# ConnWB.net
KiCad netlist of a schematic drawn in Altium Designer
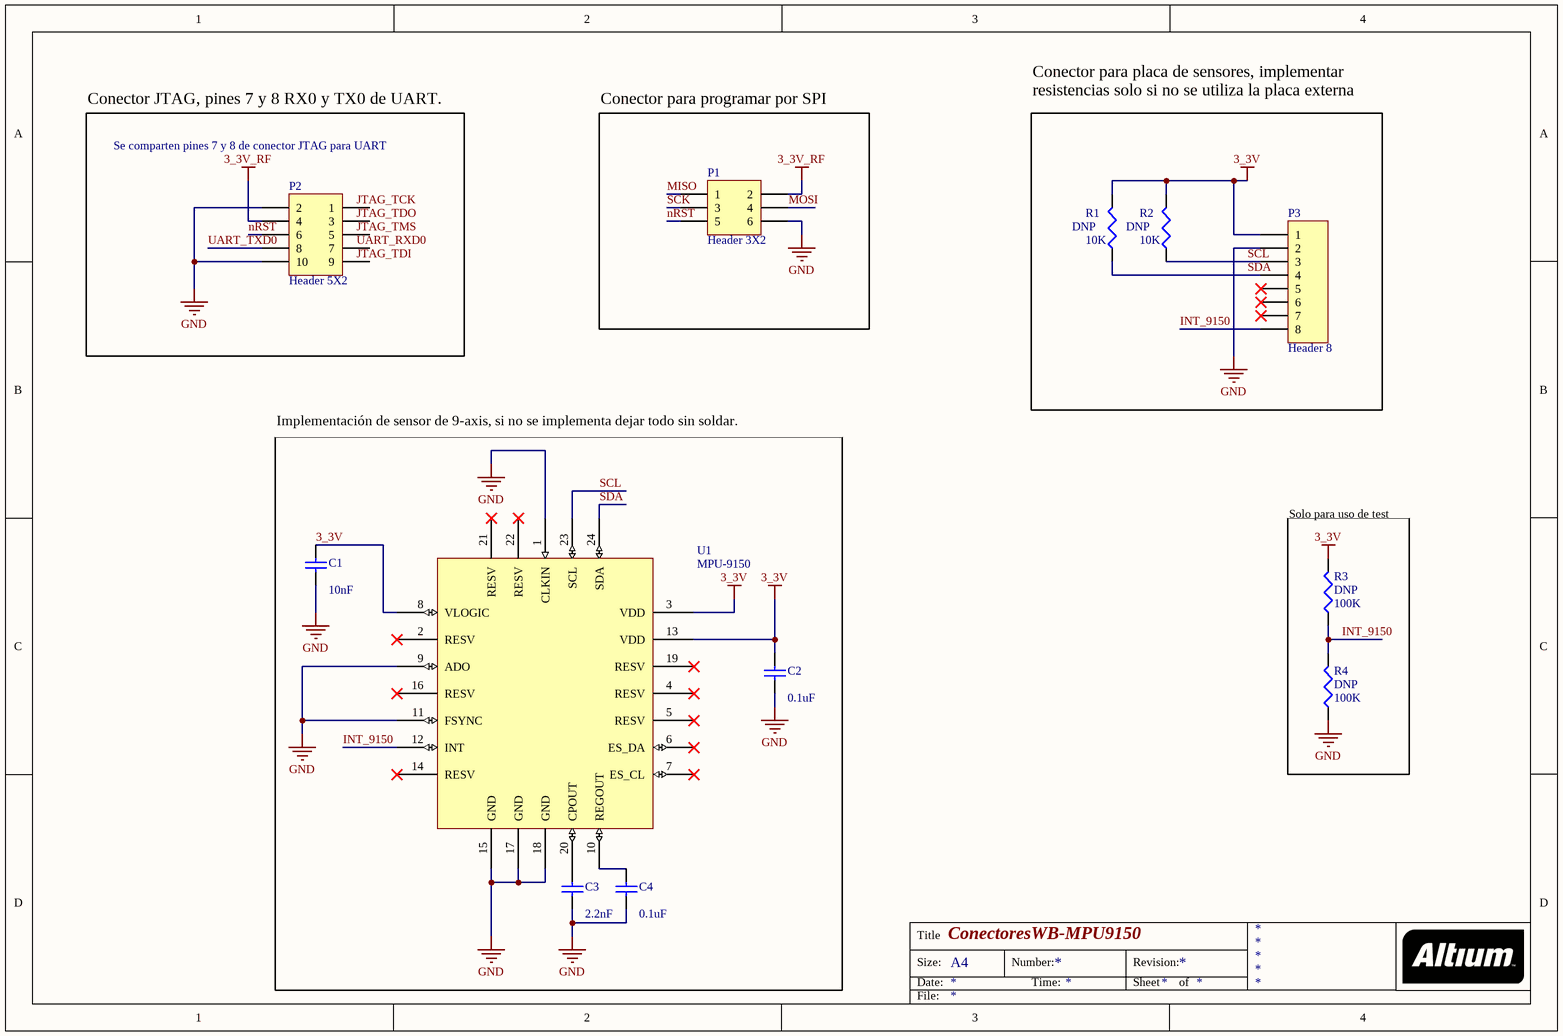
[diagram p0: ConnWB.SchDoc]

(export (version "E")
  (design (tool "Eeschema 10.0.6"))
  (components
    (comp (ref "C1")
      (value "10nF")
      (footprint "1608[0603]")
      (description "Capacitor (Semiconductor SIM Model)")
      (fields (field (name "Comment") "Cap Semi") (field (name "PUBLISHER") "Altium Limited"))
      (libsource (lib "Miscellaneous Devices") (part "Cap Semi"))
    )
    (comp (ref "C2")
      (value "0.1uF")
      (footprint "C1206")
      (description "Capacitor (Semiconductor SIM Model)")
      (fields (field (name "Comment") "Cap Semi") (field (name "PUBLISHER") "Altium Limited"))
      (libsource (lib "Miscellaneous Devices") (part "Cap Semi"))
    )
    (comp (ref "C3")
      (value "2.2nF")
      (footprint "1608[0603]")
      (description "Capacitor (Semiconductor SIM Model)")
      (fields (field (name "Comment") "Cap Semi") (field (name "PUBLISHER") "Altium Limited"))
      (libsource (lib "Miscellaneous Devices") (part "Cap Semi"))
    )
    (comp (ref "C4")
      (value "0.1uF")
      (footprint "1608[0603]")
      (description "Capacitor (Semiconductor SIM Model)")
      (fields (field (name "Comment") "Cap Semi") (field (name "PUBLISHER") "Altium Limited"))
      (libsource (lib "Miscellaneous Devices") (part "Cap Semi"))
    )
    (comp (ref "P1")
      (value "Header 3X2")
      (footprint "HDR2X3")
      (description "Header, 3-Pin, Dual row")
      (fields (field (name "PUBLISHER") "Altium Limited"))
      (libsource (lib "Miscellaneous Connectors") (part "Header 3X2"))
    )
    (comp (ref "P2")
      (value "Header 5X2")
      (footprint "HDR2X5")
      (description "Header, 5-Pin, Dual row")
      (fields (field (name "PUBLISHER") "Altium Limited"))
      (libsource (lib "Miscellaneous Connectors") (part "Header 5X2"))
    )
    (comp (ref "P3")
      (value "Header 8")
      (footprint "Conector8")
      (description "Header, 8-Pin")
      (fields (field (name "PUBLISHER") "Altium Limited"))
      (libsource (lib "Miscellaneous Connectors") (part "Header 8"))
    )
    (comp (ref "R1")
      (value "DNP")
      (footprint "6-0805_M")
      (description "Resistor")
      (fields (field (name "ALTIUM_VALUE") "10K") (field (name "PUBLISHER") "Altium Limited"))
      (libsource (lib "Miscellaneous Devices") (part "Res3"))
    )
    (comp (ref "R2")
      (value "DNP")
      (footprint "6-0805_M")
      (description "Resistor")
      (fields (field (name "ALTIUM_VALUE") "10K") (field (name "PUBLISHER") "Altium Limited"))
      (libsource (lib "Miscellaneous Devices") (part "Res3"))
    )
    (comp (ref "R3")
      (value "DNP")
      (footprint "6-0805_M")
      (description "Resistor")
      (fields (field (name "ALTIUM_VALUE") "100K") (field (name "PUBLISHER") "Altium Limited"))
      (libsource (lib "Miscellaneous Devices") (part "Res3"))
    )
    (comp (ref "R4")
      (value "DNP")
      (footprint "6-0805_M")
      (description "Resistor")
      (fields (field (name "ALTIUM_VALUE") "100K") (field (name "PUBLISHER") "Altium Limited"))
      (libsource (lib "Miscellaneous Devices") (part "Res3"))
    )
    (comp (ref "U1")
      (value "MPU-9150")
      (footprint "QFP-24")
      (description "Integrated 9-axis MotionTracking device")
      (libsource (lib "sch_comp") (part "MPU-9150"))
    )
  )
  (nets
    (net (code "1") (name "/INT_9150") (class "Default")
      (node (ref "P3") (pin "8") (pinfunction "8_8") (pintype "passive"))
      (node (ref "R3") (pin "1") (pinfunction "1_1") (pintype "passive"))
      (node (ref "R4") (pin "2") (pinfunction "2_2") (pintype "passive"))
      (node (ref "U1") (pin "12") (pinfunction "INT_12") (pintype "bidirectional"))
    )
    (net (code "6") (name "/MISO") (class "Default")
      (node (ref "P1") (pin "1") (pinfunction "1_1") (pintype "passive"))
    )
    (net (code "7") (name "/MOSI") (class "Default")
      (node (ref "P1") (pin "4") (pinfunction "4_4") (pintype "passive"))
    )
    (net (code "8") (name "/SCK") (class "Default")
      (node (ref "P1") (pin "3") (pinfunction "3_3") (pintype "passive"))
    )
    (net (code "9") (name "/SCL") (class "Default")
      (node (ref "P3") (pin "3") (pinfunction "3_3") (pintype "passive"))
      (node (ref "R2") (pin "1") (pinfunction "1_1") (pintype "passive"))
      (node (ref "U1") (pin "23") (pinfunction "SCL_23") (pintype "bidirectional"))
    )
    (net (code "10") (name "/SDA") (class "Default")
      (node (ref "P3") (pin "4") (pinfunction "4_4") (pintype "passive"))
      (node (ref "R1") (pin "1") (pinfunction "1_1") (pintype "passive"))
      (node (ref "U1") (pin "24") (pinfunction "SDA_24") (pintype "bidirectional"))
    )
    (net (code "12") (name "/UART_TXD0") (class "Default")
      (node (ref "P2") (pin "8") (pinfunction "8_8") (pintype "passive"))
    )
    (net (code "13") (name "/nRST") (class "Default")
      (node (ref "P1") (pin "5") (pinfunction "5_5") (pintype "passive"))
      (node (ref "P2") (pin "6") (pinfunction "6_6") (pintype "passive"))
    )
    (net (code "14") (name "3_3V") (class "Default")
      (node (ref "C1") (pin "2") (pinfunction "2_2") (pintype "passive"))
      (node (ref "C2") (pin "1") (pinfunction "1_1") (pintype "passive"))
      (node (ref "P3") (pin "1") (pinfunction "1_1") (pintype "passive"))
      (node (ref "R1") (pin "2") (pinfunction "2_2") (pintype "passive"))
      (node (ref "R2") (pin "2") (pinfunction "2_2") (pintype "passive"))
      (node (ref "R3") (pin "2") (pinfunction "2_2") (pintype "passive"))
      (node (ref "U1") (pin "13") (pinfunction "VDD_13") (pintype "power_in"))
      (node (ref "U1") (pin "3") (pinfunction "VDD_3") (pintype "power_in"))
      (node (ref "U1") (pin "8") (pinfunction "VLOGIC_8") (pintype "bidirectional"))
    )
    (net (code "15") (name "3_3V_RF") (class "Default")
      (node (ref "P1") (pin "2") (pinfunction "2_2") (pintype "passive"))
      (node (ref "P2") (pin "4") (pinfunction "4_4") (pintype "passive"))
    )
    (net (code "16") (name "GND") (class "Default")
      (node (ref "C1") (pin "1") (pinfunction "1_1") (pintype "passive"))
      (node (ref "C2") (pin "2") (pinfunction "2_2") (pintype "passive"))
      (node (ref "C3") (pin "1") (pinfunction "1_1") (pintype "passive"))
      (node (ref "C4") (pin "1") (pinfunction "1_1") (pintype "passive"))
      (node (ref "P1") (pin "6") (pinfunction "6_6") (pintype "passive"))
      (node (ref "P2") (pin "10") (pinfunction "10_10") (pintype "passive"))
      (node (ref "P2") (pin "2") (pinfunction "2_2") (pintype "passive"))
      (node (ref "P3") (pin "2") (pinfunction "2_2") (pintype "passive"))
      (node (ref "R4") (pin "1") (pinfunction "1_1") (pintype "passive"))
      (node (ref "U1") (pin "1") (pinfunction "CLKIN_1") (pintype "input"))
      (node (ref "U1") (pin "11") (pinfunction "FSYNC_11") (pintype "bidirectional"))
      (node (ref "U1") (pin "15") (pinfunction "GND_15") (pintype "power_in"))
      (node (ref "U1") (pin "17") (pinfunction "GND_17") (pintype "power_in"))
      (node (ref "U1") (pin "18") (pinfunction "GND_18") (pintype "power_in"))
      (node (ref "U1") (pin "9") (pinfunction "ADO_9") (pintype "bidirectional"))
    )
    (net (code "17") (name "Net-(U1-CPOUT)") (class "Default")
      (node (ref "C3") (pin "2") (pinfunction "2_2") (pintype "passive"))
      (node (ref "U1") (pin "20") (pinfunction "CPOUT_20") (pintype "bidirectional"))
    )
    (net (code "18") (name "Net-(U1-REGOUT)") (class "Default")
      (node (ref "C4") (pin "2") (pinfunction "2_2") (pintype "passive"))
      (node (ref "U1") (pin "10") (pinfunction "REGOUT_10") (pintype "bidirectional"))
    )
    (net (code "19") (name "unconnected-(P2-Pad1)") (class "Default")
      (node (ref "P2") (pin "1") (pinfunction "1_1") (pintype "passive"))
    )
    (net (code "20") (name "unconnected-(P2-Pad3)") (class "Default")
      (node (ref "P2") (pin "3") (pinfunction "3_3") (pintype "passive"))
    )
    (net (code "21") (name "unconnected-(P2-Pad5)") (class "Default")
      (node (ref "P2") (pin "5") (pinfunction "5_5") (pintype "passive"))
    )
    (net (code "22") (name "unconnected-(P2-Pad7)") (class "Default")
      (node (ref "P2") (pin "7") (pinfunction "7_7") (pintype "passive"))
    )
    (net (code "23") (name "unconnected-(P2-Pad9)") (class "Default")
      (node (ref "P2") (pin "9") (pinfunction "9_9") (pintype "passive"))
    )
    (net (code "24") (name "unconnected-(P3-Pad5)") (class "Default")
      (node (ref "P3") (pin "5") (pinfunction "5_5") (pintype "passive+no_connect"))
    )
    (net (code "25") (name "unconnected-(P3-Pad6)") (class "Default")
      (node (ref "P3") (pin "6") (pinfunction "6_6") (pintype "passive+no_connect"))
    )
    (net (code "26") (name "unconnected-(P3-Pad7)") (class "Default")
      (node (ref "P3") (pin "7") (pinfunction "7_7") (pintype "passive+no_connect"))
    )
    (net (code "27") (name "unconnected-(U1-ES_CL-Pad7)") (class "Default")
      (node (ref "U1") (pin "7") (pinfunction "ES_CL_7") (pintype "bidirectional+no_connect"))
    )
    (net (code "28") (name "unconnected-(U1-ES_DA-Pad6)") (class "Default")
      (node (ref "U1") (pin "6") (pinfunction "ES_DA_6") (pintype "bidirectional+no_connect"))
    )
    (net (code "29") (name "unconnected-(U1-RESV-Pad2)") (class "Default")
      (node (ref "U1") (pin "2") (pinfunction "RESV_2") (pintype "passive+no_connect"))
    )
    (net (code "30") (name "unconnected-(U1-RESV-Pad4)") (class "Default")
      (node (ref "U1") (pin "4") (pinfunction "RESV_4") (pintype "passive+no_connect"))
    )
    (net (code "31") (name "unconnected-(U1-RESV-Pad5)") (class "Default")
      (node (ref "U1") (pin "5") (pinfunction "RESV_5") (pintype "passive+no_connect"))
    )
    (net (code "32") (name "unconnected-(U1-RESV-Pad14)") (class "Default")
      (node (ref "U1") (pin "14") (pinfunction "RESV_14") (pintype "passive+no_connect"))
    )
    (net (code "33") (name "unconnected-(U1-RESV-Pad16)") (class "Default")
      (node (ref "U1") (pin "16") (pinfunction "RESV_16") (pintype "passive+no_connect"))
    )
    (net (code "34") (name "unconnected-(U1-RESV-Pad19)") (class "Default")
      (node (ref "U1") (pin "19") (pinfunction "RESV_19") (pintype "passive+no_connect"))
    )
    (net (code "35") (name "unconnected-(U1-RESV-Pad21)") (class "Default")
      (node (ref "U1") (pin "21") (pinfunction "RESV_21") (pintype "passive+no_connect"))
    )
    (net (code "36") (name "unconnected-(U1-RESV-Pad22)") (class "Default")
      (node (ref "U1") (pin "22") (pinfunction "RESV_22") (pintype "passive+no_connect"))
    )
  )
)
